# PWMled.net
KiCad netlist of a schematic drawn in EAGLE
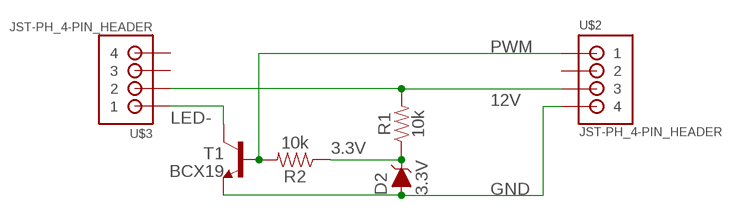
[diagram p0: schematic, sheet 1]

(export (version "E")
  (design (tool "Eeschema 10.0.6"))
  (components
    (comp (ref "D2")
      (value "3.3V")
      (footprint "eagle-import:SOD-323")
      (libsource (lib "eagle-import") (part "DIODE-ZENER-MM3Z3V3T1G"))
    )
    (comp (ref "R1")
      (value "10k")
      (footprint "eagle-import:0603")
      (libsource (lib "eagle-import") (part "10KOHM-0603-1/10W-1%"))
    )
    (comp (ref "R2")
      (value "10k")
      (footprint "eagle-import:0603")
      (libsource (lib "eagle-import") (part "10KOHM-0603-1/10W-1%"))
    )
    (comp (ref "T1")
      (value "BCX19")
      (footprint "eagle-import:SOT23")
      (libsource (lib "eagle-import") (part "BCX19"))
    )
    (comp (ref "U$2")
      (value "JST-PH_4-PIN_HEADER")
      (footprint "eagle-import:JST_B4B-PH_HEADER")
      (libsource (lib "eagle-import") (part "JST-PH_4-PIN_HEADER"))
    )
    (comp (ref "U$3")
      (value "JST-PH_4-PIN_HEADER")
      (footprint "eagle-import:JST_B4B-PH_HEADER")
      (libsource (lib "eagle-import") (part "JST-PH_4-PIN_HEADER"))
    )
  )
  (nets
    (net (code "1") (name "/3.3V") (class "Default")
      (node (ref "D2") (pin "C") (pinfunction "C_C") (pintype "passive"))
      (node (ref "R1") (pin "1") (pinfunction "1_1") (pintype "passive"))
      (node (ref "R2") (pin "1") (pinfunction "1_1") (pintype "passive"))
    )
    (net (code "2") (name "/12V") (class "Default")
      (node (ref "R1") (pin "2") (pinfunction "2_2") (pintype "passive"))
      (node (ref "U$2") (pin "P3") (pinfunction "3_P3") (pintype "bidirectional"))
      (node (ref "U$3") (pin "P2") (pinfunction "2_P2") (pintype "bidirectional"))
    )
    (net (code "3") (name "/GND") (class "Default")
      (node (ref "D2") (pin "A") (pinfunction "A_A") (pintype "passive"))
      (node (ref "T1") (pin "2") (pinfunction "E_2") (pintype "passive"))
      (node (ref "U$2") (pin "P4") (pinfunction "4_P4") (pintype "bidirectional"))
    )
    (net (code "4") (name "/LED-") (class "Default")
      (node (ref "T1") (pin "3") (pinfunction "C_3") (pintype "passive"))
      (node (ref "U$3") (pin "P1") (pinfunction "1_P1") (pintype "bidirectional"))
    )
    (net (code "5") (name "/PWM") (class "Default")
      (node (ref "R2") (pin "2") (pinfunction "2_2") (pintype "passive"))
      (node (ref "T1") (pin "1") (pinfunction "B_1") (pintype "passive"))
      (node (ref "U$2") (pin "P1") (pinfunction "1_P1") (pintype "bidirectional"))
    )
    (net (code "6") (name "unconnected-(U$2-2-PadP2)") (class "Default")
      (node (ref "U$2") (pin "P2") (pinfunction "2_P2") (pintype "bidirectional"))
    )
    (net (code "7") (name "unconnected-(U$3-3-PadP3)") (class "Default")
      (node (ref "U$3") (pin "P3") (pinfunction "3_P3") (pintype "bidirectional"))
    )
    (net (code "8") (name "unconnected-(U$3-4-PadP4)") (class "Default")
      (node (ref "U$3") (pin "P4") (pinfunction "4_P4") (pintype "bidirectional"))
    )
  )
)
